# Interface.net
KiCad netlist of a schematic drawn in Altium Designer
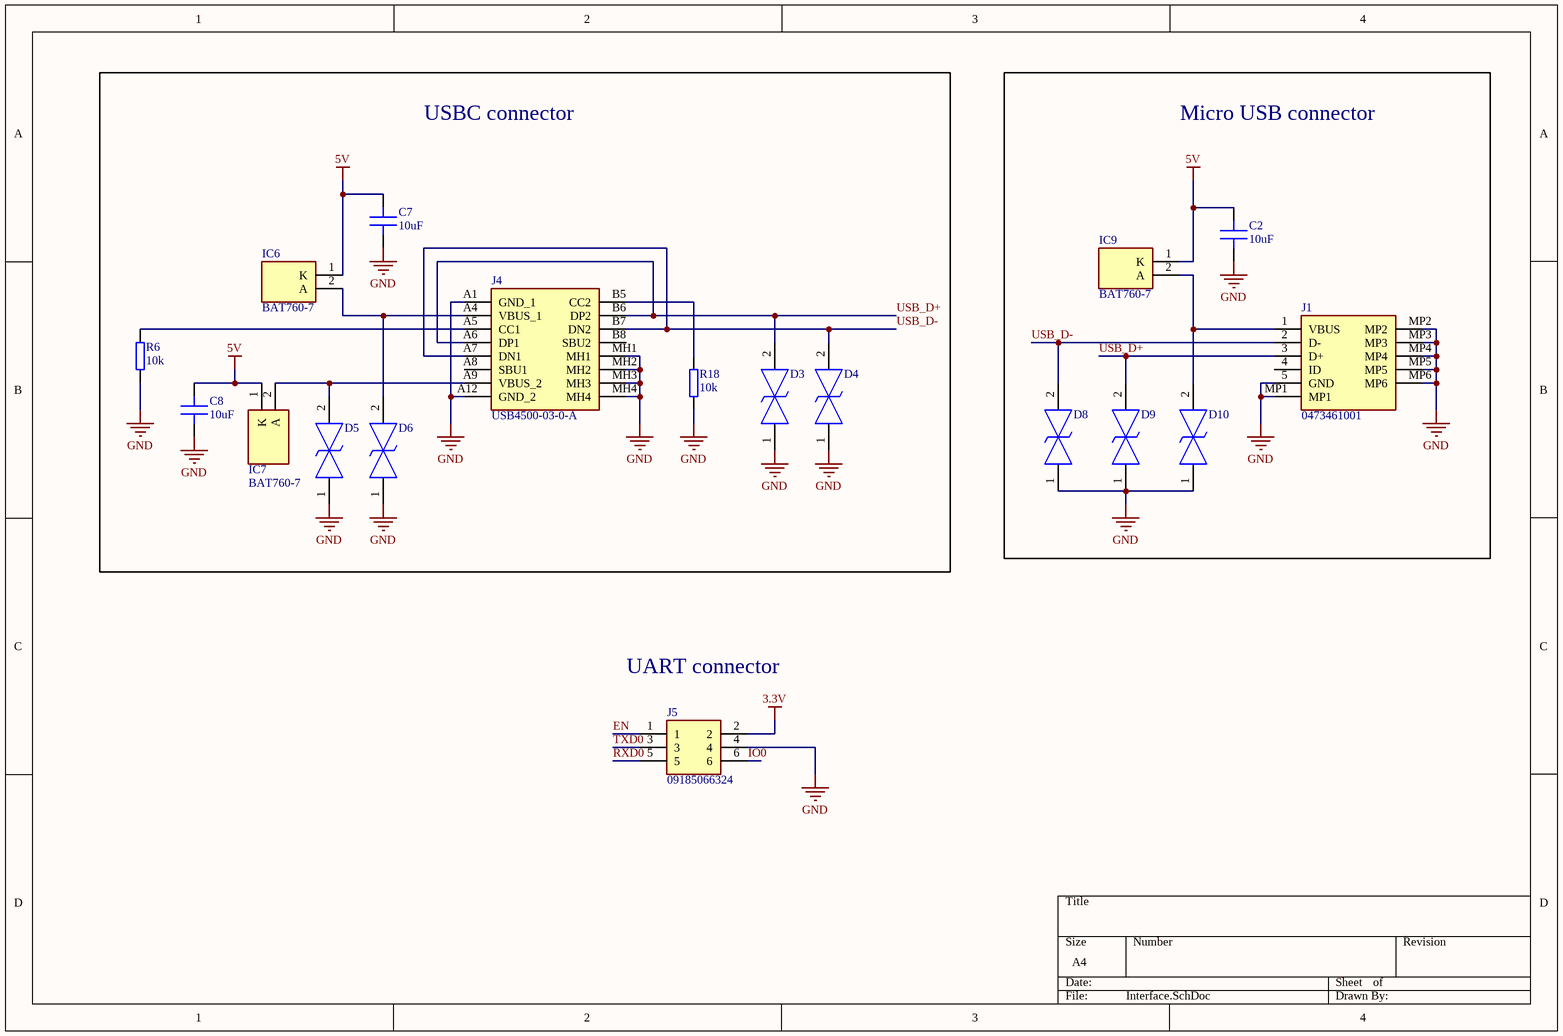
[diagram p0: Interface.SchDoc]

(export (version "E")
  (design (tool "Eeschema 10.0.6"))
  (components
    (comp (ref "C2")
      (value "10uF")
      (footprint "C 0402")
      (description "MLCC Capacitor")
      (libsource (lib "Components") (part "Capacitor"))
    )
    (comp (ref "C7")
      (value "10uF")
      (footprint "C 0402")
      (description "MLCC Capacitor")
      (libsource (lib "Components") (part "Capacitor"))
    )
    (comp (ref "C8")
      (value "10uF")
      (footprint "C 0402")
      (description "MLCC Capacitor")
      (libsource (lib "Components") (part "Capacitor"))
    )
    (comp (ref "D3")
      (value "LESD5D5.0CT1G")
      (footprint "SamacSys:LESD5D50CT1G")
      (description "TVS Diode (Bi-directional)")
      (libsource (lib "caravan_sch_lib") (part "LESD5D5.0CT1G"))
    )
    (comp (ref "D4")
      (value "LESD5D5.0CT1G")
      (footprint "SamacSys:LESD5D50CT1G")
      (description "TVS Diode (Bi-directional)")
      (libsource (lib "caravan_sch_lib") (part "LESD5D5.0CT1G"))
    )
    (comp (ref "D5")
      (value "LESD5D5.0CT1G")
      (footprint "SamacSys:LESD5D50CT1G")
      (description "TVS Diode (Bi-directional)")
      (libsource (lib "caravan_sch_lib") (part "LESD5D5.0CT1G"))
    )
    (comp (ref "D6")
      (value "LESD5D5.0CT1G")
      (footprint "SamacSys:LESD5D50CT1G")
      (description "TVS Diode (Bi-directional)")
      (libsource (lib "caravan_sch_lib") (part "LESD5D5.0CT1G"))
    )
    (comp (ref "D8")
      (value "LESD5D5.0CT1G")
      (footprint "SamacSys:LESD5D50CT1G")
      (description "TVS Diode (Bi-directional)")
      (libsource (lib "caravan_sch_lib") (part "LESD5D5.0CT1G"))
    )
    (comp (ref "D9")
      (value "LESD5D5.0CT1G")
      (footprint "SamacSys:LESD5D50CT1G")
      (description "TVS Diode (Bi-directional)")
      (libsource (lib "caravan_sch_lib") (part "LESD5D5.0CT1G"))
    )
    (comp (ref "D10")
      (value "LESD5D5.0CT1G")
      (footprint "SamacSys:LESD5D50CT1G")
      (description "TVS Diode (Bi-directional)")
      (libsource (lib "caravan_sch_lib") (part "LESD5D5.0CT1G"))
    )
    (comp (ref "IC6")
      (value "BAT760-7")
      (footprint "SamacSys:SOD2513X120N")
      (description "Integrated Circuit")
      (libsource (lib "caravan_sch_lib") (part "BAT760-7"))
    )
    (comp (ref "IC7")
      (value "BAT760-7")
      (footprint "SamacSys:SOD2513X120N")
      (description "Integrated Circuit")
      (libsource (lib "") (part "BAT760-7_1"))
    )
    (comp (ref "IC9")
      (value "BAT760-7")
      (footprint "SamacSys:SOD2513X120N")
      (description "Integrated Circuit")
      (libsource (lib "caravan_sch_lib") (part "BAT760-7"))
    )
    (comp (ref "J1")
      (value "0473461001")
      (footprint "SamacSys:0473461001")
      (description "Connector")
      (libsource (lib "*") (part "0473461001"))
    )
    (comp (ref "J4")
      (value "USB4500-03-0-A")
      (footprint "SamacSys:USB4500030A")
      (description "Connector")
      (fields (field (name "MOUSER PART NUMBER") "640-USB4500030A"))
      (libsource (lib "caravan_sch_lib") (part "USB4500-03-0-A"))
    )
    (comp (ref "J5")
      (value "09185066324")
      (footprint "SamacSys:09185066324")
      (description "Connector")
      (fields (field (name "MOUSER PART NUMBER") "617-09185066324"))
      (libsource (lib "lf_esp_sch_lib") (part "09185066324"))
    )
    (comp (ref "R6")
      (value "10k")
      (footprint "R 0402")
      (description "General pourpouse resistor")
      (libsource (lib "Components") (part "Resistor"))
    )
    (comp (ref "R18")
      (value "10k")
      (footprint "R 0402")
      (description "General pourpouse resistor")
      (libsource (lib "Components") (part "Resistor"))
    )
  )
  (nets
    (net (code "1") (name "/EN") (class "Default")
      (node (ref "J5") (pin "1") (pinfunction "1_1") (pintype "passive"))
    )
    (net (code "2") (name "/IO0") (class "Default")
      (node (ref "J5") (pin "6") (pinfunction "6_6") (pintype "passive"))
    )
    (net (code "3") (name "/RXD0") (class "Default")
      (node (ref "J5") (pin "5") (pinfunction "5_5") (pintype "passive"))
    )
    (net (code "4") (name "/TXD0") (class "Default")
      (node (ref "J5") (pin "3") (pinfunction "3_3") (pintype "passive"))
    )
    (net (code "5") (name "/USB_D+") (class "Default")
      (node (ref "D3") (pin "2") (pinfunction "2_2") (pintype "passive"))
      (node (ref "D9") (pin "2") (pinfunction "2_2") (pintype "passive"))
      (node (ref "J1") (pin "3") (pinfunction "D+_3") (pintype "passive"))
      (node (ref "J4") (pin "A6") (pinfunction "DP1_A6") (pintype "passive"))
      (node (ref "J4") (pin "B6") (pinfunction "DP2_B6") (pintype "passive"))
    )
    (net (code "6") (name "/USB_D-") (class "Default")
      (node (ref "D4") (pin "2") (pinfunction "2_2") (pintype "passive"))
      (node (ref "D8") (pin "2") (pinfunction "2_2") (pintype "passive"))
      (node (ref "J1") (pin "2") (pinfunction "D-_2") (pintype "passive"))
      (node (ref "J4") (pin "A7") (pinfunction "DN1_A7") (pintype "passive"))
      (node (ref "J4") (pin "B7") (pinfunction "DN2_B7") (pintype "passive"))
    )
    (net (code "7") (name "3.3V") (class "Default")
      (node (ref "J5") (pin "2") (pinfunction "2_2") (pintype "passive"))
    )
    (net (code "8") (name "5V") (class "Default")
      (node (ref "C2") (pin "1") (pinfunction "1_1") (pintype "passive"))
      (node (ref "C7") (pin "1") (pinfunction "1_1") (pintype "passive"))
      (node (ref "C8") (pin "1") (pinfunction "1_1") (pintype "passive"))
      (node (ref "IC6") (pin "1") (pinfunction "K_1") (pintype "passive"))
      (node (ref "IC7") (pin "1") (pinfunction "K_1") (pintype "passive"))
      (node (ref "IC9") (pin "1") (pinfunction "K_1") (pintype "passive"))
    )
    (net (code "9") (name "GND") (class "Default")
      (node (ref "C2") (pin "2") (pinfunction "2_2") (pintype "passive"))
      (node (ref "C7") (pin "2") (pinfunction "2_2") (pintype "passive"))
      (node (ref "C8") (pin "2") (pinfunction "2_2") (pintype "passive"))
      (node (ref "D10") (pin "1") (pinfunction "1_1") (pintype "passive"))
      (node (ref "D3") (pin "1") (pinfunction "1_1") (pintype "passive"))
      (node (ref "D4") (pin "1") (pinfunction "1_1") (pintype "passive"))
      (node (ref "D5") (pin "1") (pinfunction "1_1") (pintype "passive"))
      (node (ref "D6") (pin "1") (pinfunction "1_1") (pintype "passive"))
      (node (ref "D8") (pin "1") (pinfunction "1_1") (pintype "passive"))
      (node (ref "D9") (pin "1") (pinfunction "1_1") (pintype "passive"))
      (node (ref "J1") (pin "5") (pinfunction "GND_5") (pintype "passive"))
      (node (ref "J1") (pin "MP1") (pinfunction "MP1_MP1") (pintype "passive"))
      (node (ref "J1") (pin "MP2") (pinfunction "MP2_MP2") (pintype "passive"))
      (node (ref "J1") (pin "MP3") (pinfunction "MP3_MP3") (pintype "passive"))
      (node (ref "J1") (pin "MP4") (pinfunction "MP4_MP4") (pintype "passive"))
      (node (ref "J1") (pin "MP5") (pinfunction "MP5_MP5") (pintype "passive"))
      (node (ref "J1") (pin "MP6") (pinfunction "MP6_MP6") (pintype "passive"))
      (node (ref "J4") (pin "A1") (pinfunction "GND_1_A1") (pintype "passive"))
      (node (ref "J4") (pin "A12") (pinfunction "GND_2_A12") (pintype "passive"))
      (node (ref "J4") (pin "MH1") (pinfunction "MH1_MH1") (pintype "passive"))
      (node (ref "J4") (pin "MH2") (pinfunction "MH2_MH2") (pintype "passive"))
      (node (ref "J4") (pin "MH3") (pinfunction "MH3_MH3") (pintype "passive"))
      (node (ref "J4") (pin "MH4") (pinfunction "MH4_MH4") (pintype "passive"))
      (node (ref "J5") (pin "4") (pinfunction "4_4") (pintype "passive"))
      (node (ref "R18") (pin "1") (pinfunction "1_1") (pintype "passive"))
      (node (ref "R6") (pin "1") (pinfunction "1_1") (pintype "passive"))
    )
    (net (code "10") (name "Net-(IC6-A)") (class "Default")
      (node (ref "D6") (pin "2") (pinfunction "2_2") (pintype "passive"))
      (node (ref "IC6") (pin "2") (pinfunction "A_2") (pintype "passive"))
      (node (ref "J4") (pin "A4") (pinfunction "VBUS_1_A4") (pintype "passive"))
    )
    (net (code "11") (name "Net-(IC7-A)") (class "Default")
      (node (ref "D5") (pin "2") (pinfunction "2_2") (pintype "passive"))
      (node (ref "IC7") (pin "2") (pinfunction "A_2") (pintype "passive"))
      (node (ref "J4") (pin "A9") (pinfunction "VBUS_2_A9") (pintype "passive"))
    )
    (net (code "12") (name "Net-(IC9-A)") (class "Default")
      (node (ref "D10") (pin "2") (pinfunction "2_2") (pintype "passive"))
      (node (ref "IC9") (pin "2") (pinfunction "A_2") (pintype "passive"))
      (node (ref "J1") (pin "1") (pinfunction "VBUS_1") (pintype "passive"))
    )
    (net (code "13") (name "Net-(J4-CC1)") (class "Default")
      (node (ref "J4") (pin "A5") (pinfunction "CC1_A5") (pintype "passive"))
      (node (ref "R6") (pin "2") (pinfunction "2_2") (pintype "passive"))
    )
    (net (code "14") (name "Net-(J4-CC2)") (class "Default")
      (node (ref "J4") (pin "B5") (pinfunction "CC2_B5") (pintype "passive"))
      (node (ref "R18") (pin "2") (pinfunction "2_2") (pintype "passive"))
    )
    (net (code "15") (name "unconnected-(J1-ID-Pad4)") (class "Default")
      (node (ref "J1") (pin "4") (pinfunction "ID_4") (pintype "passive"))
    )
    (net (code "16") (name "unconnected-(J4-SBU1-PadA8)") (class "Default")
      (node (ref "J4") (pin "A8") (pinfunction "SBU1_A8") (pintype "passive"))
    )
    (net (code "17") (name "unconnected-(J4-SBU2-PadB8)") (class "Default")
      (node (ref "J4") (pin "B8") (pinfunction "SBU2_B8") (pintype "passive"))
    )
  )
)
